# Sheet2.net
KiCad netlist of a schematic drawn in Altium Designer
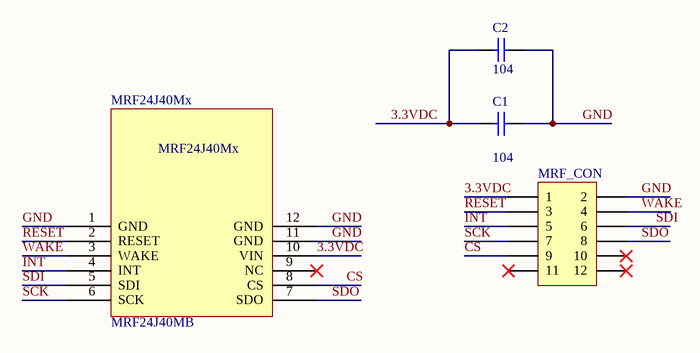
[diagram p0: Sheet2.SchDoc]

(export (version "E")
  (design (tool "Eeschema 10.0.6"))
  (components
    (comp (ref "C1")
      (value "104")
      (footprint "CN1.5")
      (description "Capacitor")
      (fields (field (name "Comment") "Cap") (field (name "PUBLISHER") "Altium Limited"))
      (libsource (lib "Miscellaneous Devices") (part "Cap"))
    )
    (comp (ref "C2")
      (value "104")
      (footprint "CN1.5")
      (description "Capacitor")
      (fields (field (name "Comment") "Cap") (field (name "PUBLISHER") "Altium Limited"))
      (libsource (lib "Miscellaneous Devices") (part "Cap"))
    )
    (comp (ref "MRF24J40Mx")
      (value "MRF24J40MB")
      (footprint "MRF24J40MB")
      (libsource (lib "syhaunguyen") (part "MRF24J40MB"))
    )
    (comp (ref "MRF_CON")
      (value "Header 6X2")
      (footprint "HDR2X6")
      (description "Header, 6-Pin, Dual row")
      (fields (field (name "PUBLISHER") "Altium Limited"))
      (libsource (lib "Miscellaneous Connectors") (part "Header 6X2"))
    )
  )
  (nets
    (net (code "1") (name "/3.3VDC") (class "Default")
      (node (ref "C1") (pin "2") (pinfunction "2_2") (pintype "passive"))
      (node (ref "C2") (pin "1") (pinfunction "1_1") (pintype "passive"))
      (node (ref "MRF24J40Mx") (pin "10") (pinfunction "VIN_10") (pintype "passive"))
      (node (ref "MRF_CON") (pin "1") (pinfunction "1_1") (pintype "passive"))
    )
    (net (code "2") (name "/CS") (class "Default")
      (node (ref "MRF24J40Mx") (pin "8") (pinfunction "CS_8") (pintype "passive"))
      (node (ref "MRF_CON") (pin "9") (pinfunction "9_9") (pintype "passive"))
    )
    (net (code "3") (name "/GND") (class "Default")
      (node (ref "C1") (pin "1") (pinfunction "1_1") (pintype "passive"))
      (node (ref "C2") (pin "2") (pinfunction "2_2") (pintype "passive"))
      (node (ref "MRF24J40Mx") (pin "1") (pinfunction "GND_1") (pintype "passive"))
      (node (ref "MRF24J40Mx") (pin "11") (pinfunction "GND_11") (pintype "passive"))
      (node (ref "MRF24J40Mx") (pin "12") (pinfunction "GND_12") (pintype "passive"))
      (node (ref "MRF_CON") (pin "2") (pinfunction "2_2") (pintype "passive"))
    )
    (net (code "4") (name "/INT") (class "Default")
      (node (ref "MRF24J40Mx") (pin "4") (pinfunction "INT_4") (pintype "passive"))
      (node (ref "MRF_CON") (pin "5") (pinfunction "5_5") (pintype "passive"))
    )
    (net (code "5") (name "/RESET") (class "Default")
      (node (ref "MRF24J40Mx") (pin "2") (pinfunction "RESET_2") (pintype "passive"))
      (node (ref "MRF_CON") (pin "3") (pinfunction "3_3") (pintype "passive"))
    )
    (net (code "6") (name "/SCK") (class "Default")
      (node (ref "MRF24J40Mx") (pin "6") (pinfunction "SCK_6") (pintype "passive"))
      (node (ref "MRF_CON") (pin "7") (pinfunction "7_7") (pintype "passive"))
    )
    (net (code "7") (name "/SDI") (class "Default")
      (node (ref "MRF24J40Mx") (pin "5") (pinfunction "SDI_5") (pintype "passive"))
      (node (ref "MRF_CON") (pin "6") (pinfunction "6_6") (pintype "passive"))
    )
    (net (code "8") (name "/SDO") (class "Default")
      (node (ref "MRF24J40Mx") (pin "7") (pinfunction "SDO_7") (pintype "passive"))
      (node (ref "MRF_CON") (pin "8") (pinfunction "8_8") (pintype "passive"))
    )
    (net (code "9") (name "/WAKE") (class "Default")
      (node (ref "MRF24J40Mx") (pin "3") (pinfunction "WAKE_3") (pintype "passive"))
      (node (ref "MRF_CON") (pin "4") (pinfunction "4_4") (pintype "passive"))
    )
    (net (code "10") (name "unconnected-(MRF24J40Mx-NC-Pad9)") (class "Default")
      (node (ref "MRF24J40Mx") (pin "9") (pinfunction "NC_9") (pintype "passive+no_connect"))
    )
    (net (code "11") (name "unconnected-(MRF_CON-Pad10)") (class "Default")
      (node (ref "MRF_CON") (pin "10") (pinfunction "10_10") (pintype "passive+no_connect"))
    )
    (net (code "12") (name "unconnected-(MRF_CON-Pad11)") (class "Default")
      (node (ref "MRF_CON") (pin "11") (pinfunction "11_11") (pintype "passive+no_connect"))
    )
    (net (code "13") (name "unconnected-(MRF_CON-Pad12)") (class "Default")
      (node (ref "MRF_CON") (pin "12") (pinfunction "12_12") (pintype "passive+no_connect"))
    )
  )
)
